# SNES1Chip_SCIC_IGR_D4_Takt.net
KiCad netlist of a schematic drawn in EAGLE
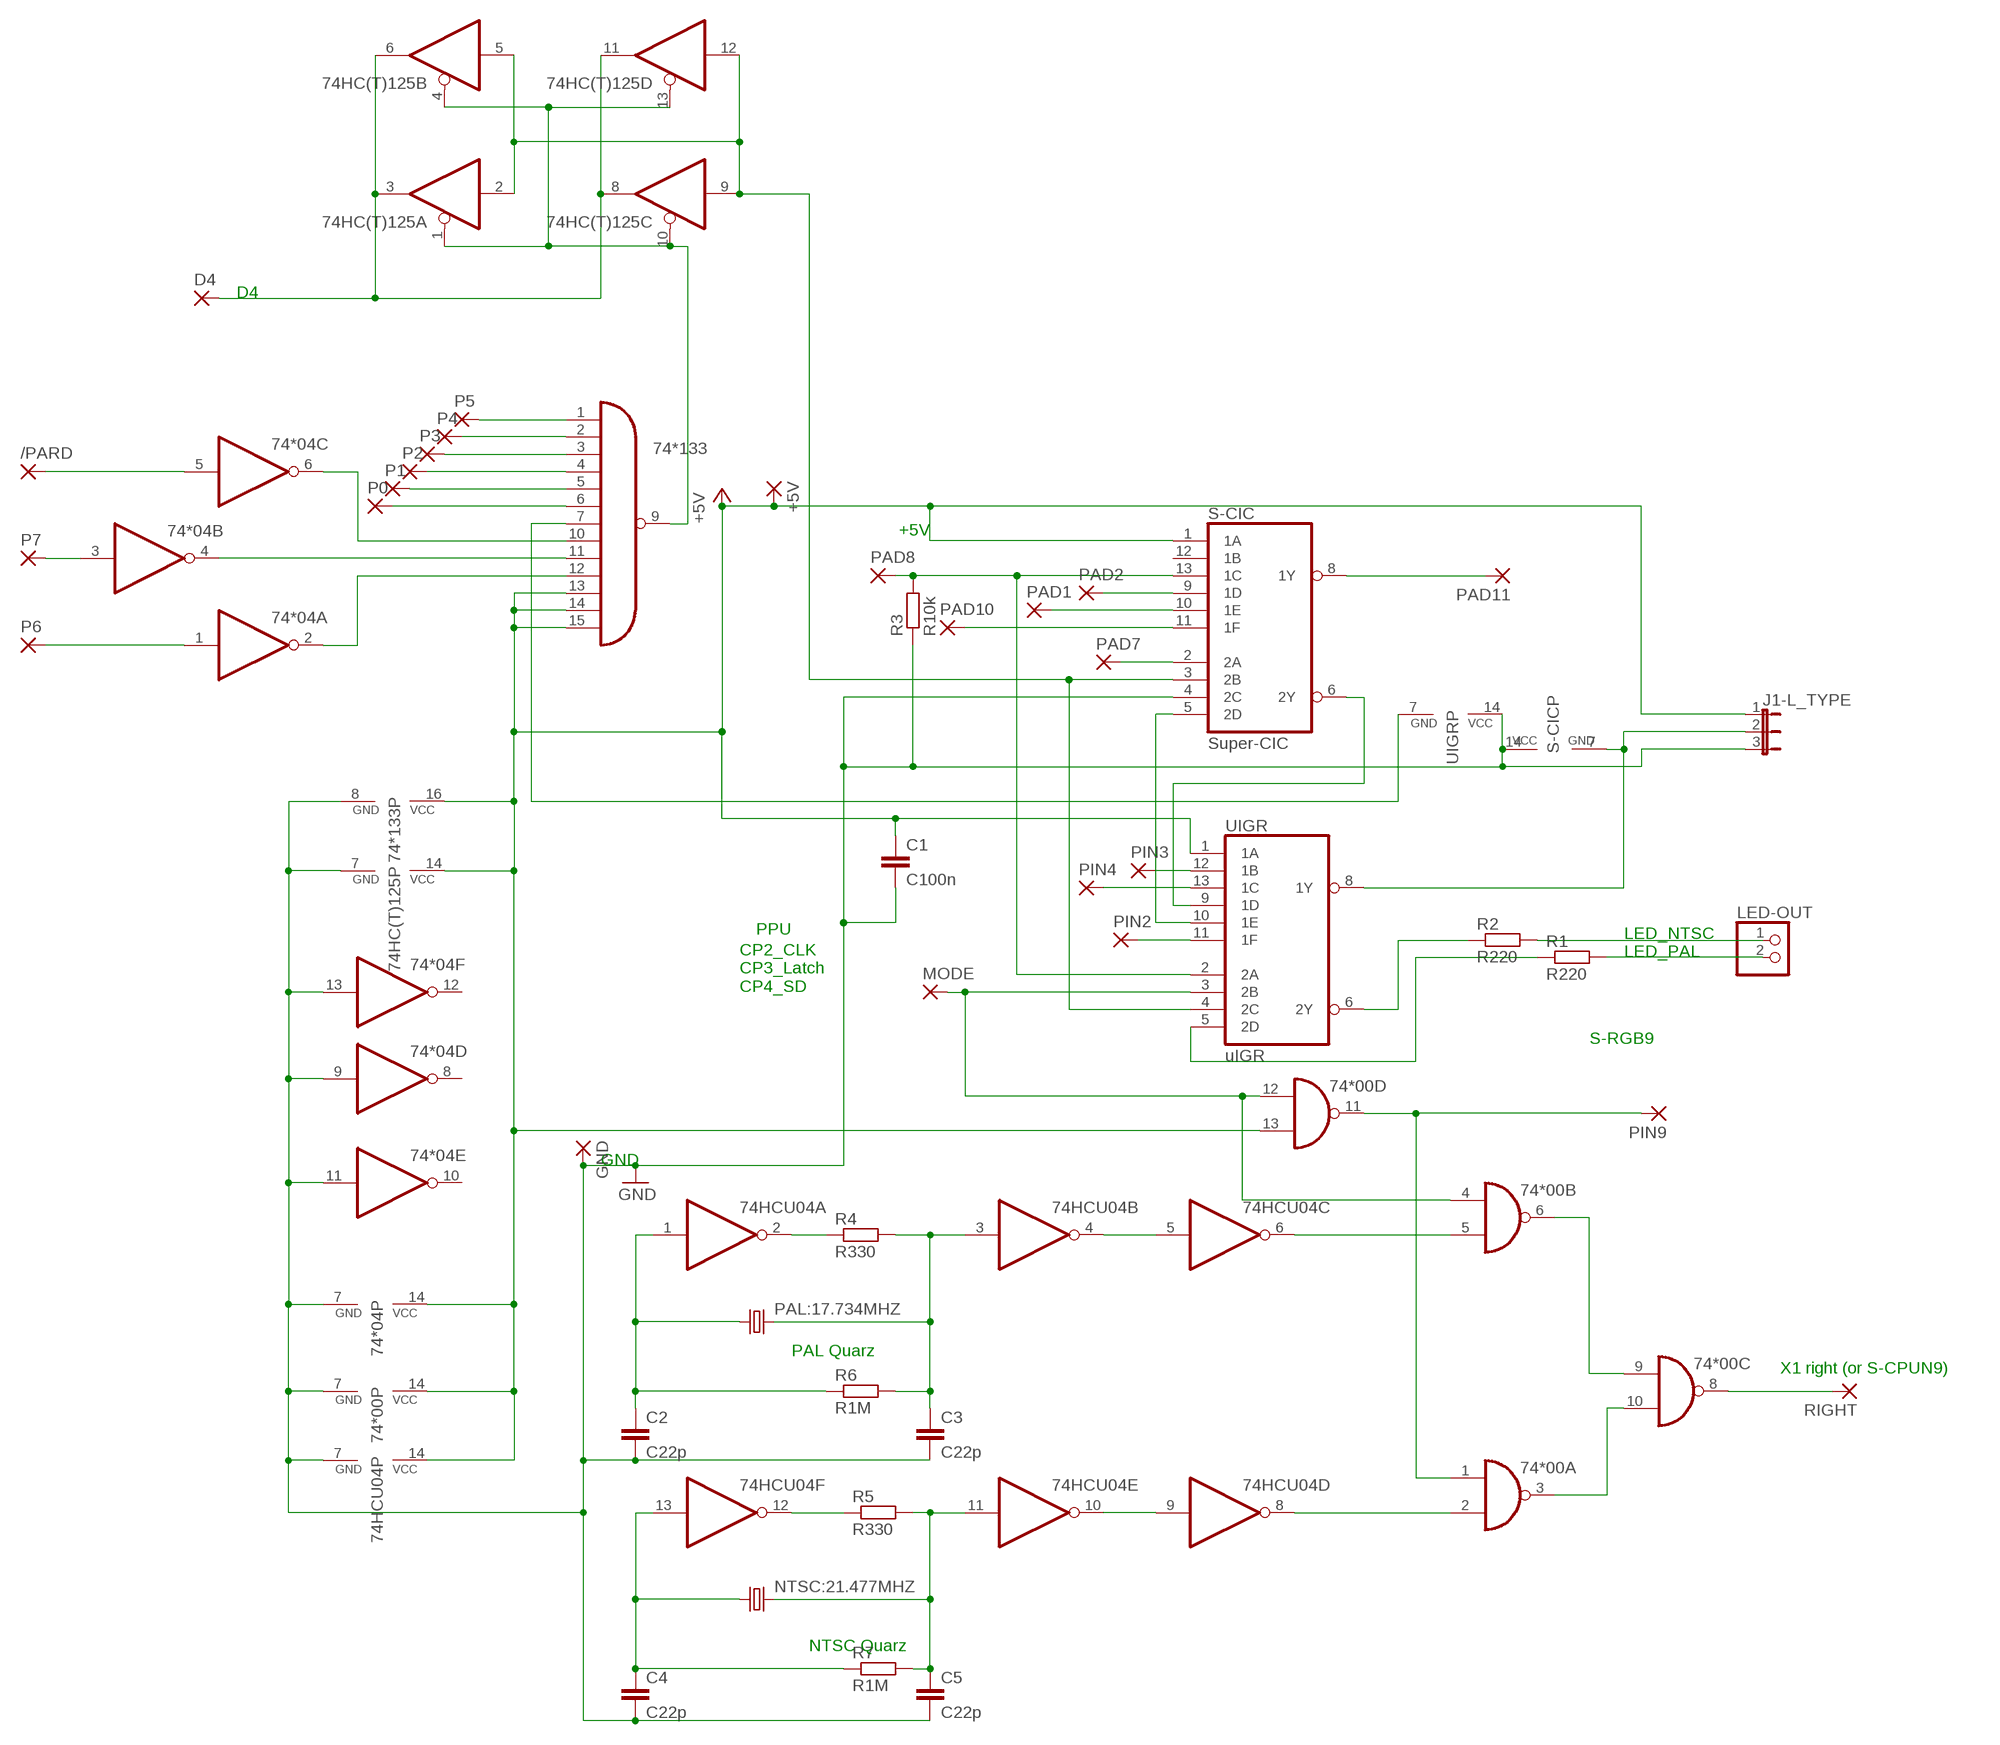
[diagram p0: schematic, sheet 1]

(export (version "E")
  (design (tool "Eeschema 10.0.6"))
  (components
    (comp (ref "+5V")
      (value "2,54/0,8")
      (footprint "eagle-import:2,54_0,8")
      (libsource (lib "eagle-import") (part "2,54/0,8"))
    )
    (comp (ref "/PARD")
      (value "2,54/0,8")
      (footprint "eagle-import:2,54_0,8")
      (libsource (lib "eagle-import") (part "2,54/0,8"))
    )
    (comp (ref "74*00")
      (value "7400D")
      (footprint "eagle-import:SO14")
      (libsource (lib "eagle-import") (part "7400D"))
    )
    (comp (ref "74*04")
      (value "74S04D")
      (footprint "eagle-import:SO14")
      (libsource (lib "eagle-import") (part "7404DS"))
    )
    (comp (ref "74*133")
      (value "74S133D")
      (footprint "eagle-import:SO16")
      (libsource (lib "eagle-import") (part "74133DS"))
    )
    (comp (ref "74HC(T)125")
      (value "74HCT125D")
      (footprint "eagle-import:SO14")
      (libsource (lib "eagle-import") (part "74125DHCT"))
    )
    (comp (ref "74HCU04")
      (value "74HC04D")
      (footprint "eagle-import:SO14")
      (libsource (lib "eagle-import") (part "7404DHC"))
    )
    (comp (ref "C1")
      (value "C100n")
      (footprint "eagle-import:C0805")
      (libsource (lib "eagle-import") (part "C-EUC0805"))
    )
    (comp (ref "C2")
      (value "C22p")
      (footprint "eagle-import:C0805")
      (libsource (lib "eagle-import") (part "C-EUC0805"))
    )
    (comp (ref "C3")
      (value "C22p")
      (footprint "eagle-import:C0805")
      (libsource (lib "eagle-import") (part "C-EUC0805"))
    )
    (comp (ref "C4")
      (value "C22p")
      (footprint "eagle-import:C0805")
      (libsource (lib "eagle-import") (part "C-EUC0805"))
    )
    (comp (ref "C5")
      (value "C22p")
      (footprint "eagle-import:C0805")
      (libsource (lib "eagle-import") (part "C-EUC0805"))
    )
    (comp (ref "D4")
      (value "2,54/0,8")
      (footprint "eagle-import:2,54_0,8")
      (libsource (lib "eagle-import") (part "2,54/0,8"))
    )
    (comp (ref "GND")
      (value "2,54/0,8")
      (footprint "eagle-import:2,54_0,8")
      (libsource (lib "eagle-import") (part "2,54/0,8"))
    )
    (comp (ref "J1-L_TYPE")
      (value "JP2E")
      (footprint "eagle-import:JP2")
      (libsource (lib "eagle-import") (part "JP2E"))
    )
    (comp (ref "LED-OUT")
      (value "PINHD-1X2")
      (footprint "eagle-import:1X02")
      (libsource (lib "eagle-import") (part "PINHD-1X2"))
    )
    (comp (ref "MODE")
      (value "2,54/0,8")
      (footprint "eagle-import:2,54_0,8")
      (libsource (lib "eagle-import") (part "2,54/0,8"))
    )
    (comp (ref "NTSC:21.477MHZ")
      (value "CRYSTALHC49S")
      (footprint "eagle-import:HC49_S")
      (libsource (lib "eagle-import") (part "CRYSTALHC49S"))
    )
    (comp (ref "P0")
      (value "2,54/0,8")
      (footprint "eagle-import:2,54_0,8")
      (libsource (lib "eagle-import") (part "2,54/0,8"))
    )
    (comp (ref "P1")
      (value "2,54/0,8")
      (footprint "eagle-import:2,54_0,8")
      (libsource (lib "eagle-import") (part "2,54/0,8"))
    )
    (comp (ref "P2")
      (value "2,54/0,8")
      (footprint "eagle-import:2,54_0,8")
      (libsource (lib "eagle-import") (part "2,54/0,8"))
    )
    (comp (ref "P3")
      (value "2,54/0,8")
      (footprint "eagle-import:2,54_0,8")
      (libsource (lib "eagle-import") (part "2,54/0,8"))
    )
    (comp (ref "P4")
      (value "2,54/0,8")
      (footprint "eagle-import:2,54_0,8")
      (libsource (lib "eagle-import") (part "2,54/0,8"))
    )
    (comp (ref "P5")
      (value "2,54/0,8")
      (footprint "eagle-import:2,54_0,8")
      (libsource (lib "eagle-import") (part "2,54/0,8"))
    )
    (comp (ref "P6")
      (value "2,54/0,8")
      (footprint "eagle-import:2,54_0,8")
      (libsource (lib "eagle-import") (part "2,54/0,8"))
    )
    (comp (ref "P7")
      (value "2,54/0,8")
      (footprint "eagle-import:2,54_0,8")
      (libsource (lib "eagle-import") (part "2,54/0,8"))
    )
    (comp (ref "PAD1")
      (value "2,54/0,8")
      (footprint "eagle-import:2,54_0,8")
      (libsource (lib "eagle-import") (part "2,54/0,8"))
    )
    (comp (ref "PAD2")
      (value "2,54/0,8")
      (footprint "eagle-import:2,54_0,8")
      (libsource (lib "eagle-import") (part "2,54/0,8"))
    )
    (comp (ref "PAD7")
      (value "2,54/0,8")
      (footprint "eagle-import:2,54_0,8")
      (libsource (lib "eagle-import") (part "2,54/0,8"))
    )
    (comp (ref "PAD8")
      (value "2,54/0,8")
      (footprint "eagle-import:2,54_0,8")
      (libsource (lib "eagle-import") (part "2,54/0,8"))
    )
    (comp (ref "PAD10")
      (value "2,54/0,8")
      (footprint "eagle-import:2,54_0,8")
      (libsource (lib "eagle-import") (part "2,54/0,8"))
    )
    (comp (ref "PAD11")
      (value "2,54/0,8")
      (footprint "eagle-import:2,54_0,8")
      (libsource (lib "eagle-import") (part "2,54/0,8"))
    )
    (comp (ref "PAL:17.734MHZ")
      (value "CRYSTALHC49S")
      (footprint "eagle-import:HC49_S")
      (libsource (lib "eagle-import") (part "CRYSTALHC49S"))
    )
    (comp (ref "PIN2")
      (value "2,54/0,8")
      (footprint "eagle-import:2,54_0,8")
      (libsource (lib "eagle-import") (part "2,54/0,8"))
    )
    (comp (ref "PIN3")
      (value "2,54/0,8")
      (footprint "eagle-import:2,54_0,8")
      (libsource (lib "eagle-import") (part "2,54/0,8"))
    )
    (comp (ref "PIN4")
      (value "2,54/0,8")
      (footprint "eagle-import:2,54_0,8")
      (libsource (lib "eagle-import") (part "2,54/0,8"))
    )
    (comp (ref "PIN9")
      (value "2,54/0,8")
      (footprint "eagle-import:2,54_0,8")
      (libsource (lib "eagle-import") (part "2,54/0,8"))
    )
    (comp (ref "R1")
      (value "R220")
      (footprint "eagle-import:R0805")
      (libsource (lib "eagle-import") (part "R-EU_R0805"))
    )
    (comp (ref "R2")
      (value "R220")
      (footprint "eagle-import:R0805")
      (libsource (lib "eagle-import") (part "R-EU_R0805"))
    )
    (comp (ref "R3")
      (value "R10k")
      (footprint "eagle-import:R0805")
      (libsource (lib "eagle-import") (part "R-EU_R0805"))
    )
    (comp (ref "R4")
      (value "R330")
      (footprint "eagle-import:R0805")
      (libsource (lib "eagle-import") (part "R-EU_R0805"))
    )
    (comp (ref "R5")
      (value "R330")
      (footprint "eagle-import:R0805")
      (libsource (lib "eagle-import") (part "R-EU_R0805"))
    )
    (comp (ref "R6")
      (value "R1M")
      (footprint "eagle-import:R0805")
      (libsource (lib "eagle-import") (part "R-EU_R0805"))
    )
    (comp (ref "R7")
      (value "R1M")
      (footprint "eagle-import:R0805")
      (libsource (lib "eagle-import") (part "R-EU_R0805"))
    )
    (comp (ref "RIGHT")
      (value "2,54/0,8")
      (footprint "eagle-import:2,54_0,8")
      (libsource (lib "eagle-import") (part "2,54/0,8"))
    )
    (comp (ref "S-CIC")
      (value "Super-CIC")
      (footprint "eagle-import:SO14")
      (libsource (lib "eagle-import") (part "7451DHC"))
    )
    (comp (ref "UIGR")
      (value "uIGR")
      (footprint "eagle-import:SO14")
      (libsource (lib "eagle-import") (part "7451DHC"))
    )
  )
  (nets
    (net (code "1") (name "+5V") (class "Default")
      (node (ref "+5V") (pin "1") (pinfunction "P_1") (pintype "passive"))
      (node (ref "74*00") (pin "13") (pinfunction "I1_13") (pintype "input"))
      (node (ref "74*00") (pin "14") (pinfunction "VCC_14") (pintype "power_in"))
      (node (ref "74*04") (pin "14") (pinfunction "VCC_14") (pintype "power_in"))
      (node (ref "74*133") (pin "13") (pinfunction "I10_13") (pintype "input"))
      (node (ref "74*133") (pin "14") (pinfunction "I11_14") (pintype "input"))
      (node (ref "74*133") (pin "15") (pinfunction "I12_15") (pintype "input"))
      (node (ref "74*133") (pin "16") (pinfunction "VCC_16") (pintype "power_in"))
      (node (ref "74HC(T)125") (pin "14") (pinfunction "VCC_14") (pintype "power_in"))
      (node (ref "74HCU04") (pin "14") (pinfunction "VCC_14") (pintype "power_in"))
      (node (ref "C1") (pin "1") (pinfunction "1_1") (pintype "passive"))
      (node (ref "J1-L_TYPE") (pin "1") (pinfunction "1_1") (pintype "passive"))
      (node (ref "S-CIC") (pin "1") (pinfunction "1A_1") (pintype "input"))
      (node (ref "UIGR") (pin "1") (pinfunction "1A_1") (pintype "input"))
    )
    (net (code "2") (name "GND") (class "Default")
      (node (ref "74*00") (pin "7") (pinfunction "GND_7") (pintype "power_in"))
      (node (ref "74*04") (pin "11") (pinfunction "I_11") (pintype "input"))
      (node (ref "74*04") (pin "13") (pinfunction "I_13") (pintype "input"))
      (node (ref "74*04") (pin "7") (pinfunction "GND_7") (pintype "power_in"))
      (node (ref "74*04") (pin "9") (pinfunction "I_9") (pintype "input"))
      (node (ref "74*133") (pin "8") (pinfunction "GND_8") (pintype "power_in"))
      (node (ref "74HC(T)125") (pin "7") (pinfunction "GND_7") (pintype "power_in"))
      (node (ref "74HCU04") (pin "7") (pinfunction "GND_7") (pintype "power_in"))
      (node (ref "C1") (pin "2") (pinfunction "2_2") (pintype "passive"))
      (node (ref "C2") (pin "2") (pinfunction "2_2") (pintype "passive"))
      (node (ref "C3") (pin "2") (pinfunction "2_2") (pintype "passive"))
      (node (ref "C4") (pin "2") (pinfunction "2_2") (pintype "passive"))
      (node (ref "C5") (pin "2") (pinfunction "2_2") (pintype "passive"))
      (node (ref "GND") (pin "1") (pinfunction "P_1") (pintype "passive"))
      (node (ref "J1-L_TYPE") (pin "3") (pinfunction "3_3") (pintype "passive"))
      (node (ref "R3") (pin "1") (pinfunction "1_1") (pintype "passive"))
      (node (ref "S-CIC") (pin "14") (pinfunction "VCC_14") (pintype "power_in"))
      (node (ref "S-CIC") (pin "4") (pinfunction "2C_4") (pintype "input"))
      (node (ref "UIGR") (pin "14") (pinfunction "VCC_14") (pintype "power_in"))
    )
    (net (code "3") (name "Net-(/PARD-P)") (class "Default")
      (node (ref "/PARD") (pin "1") (pinfunction "P_1") (pintype "passive"))
      (node (ref "74*04") (pin "5") (pinfunction "I_5") (pintype "input"))
    )
    (net (code "4") (name "Net-(74*00A-I0)") (class "Default")
      (node (ref "74*00") (pin "1") (pinfunction "I0_1") (pintype "input"))
      (node (ref "74*00") (pin "11") (pinfunction "O_11") (pintype "output"))
      (node (ref "PIN9") (pin "1") (pinfunction "P_1") (pintype "passive"))
    )
    (net (code "5") (name "Net-(74*00A-I1)") (class "Default")
      (node (ref "74*00") (pin "2") (pinfunction "I1_2") (pintype "input"))
      (node (ref "74HCU04") (pin "8") (pinfunction "O_8") (pintype "output"))
    )
    (net (code "6") (name "Net-(74*00A-O)") (class "Default")
      (node (ref "74*00") (pin "10") (pinfunction "I1_10") (pintype "input"))
      (node (ref "74*00") (pin "3") (pinfunction "O_3") (pintype "output"))
    )
    (net (code "7") (name "Net-(74*00B-I0)") (class "Default")
      (node (ref "74*00") (pin "12") (pinfunction "I0_12") (pintype "input"))
      (node (ref "74*00") (pin "4") (pinfunction "I0_4") (pintype "input"))
      (node (ref "MODE") (pin "1") (pinfunction "P_1") (pintype "passive"))
      (node (ref "UIGR") (pin "3") (pinfunction "2B_3") (pintype "input"))
    )
    (net (code "8") (name "Net-(74*00B-I1)") (class "Default")
      (node (ref "74*00") (pin "5") (pinfunction "I1_5") (pintype "input"))
      (node (ref "74HCU04") (pin "6") (pinfunction "O_6") (pintype "output"))
    )
    (net (code "9") (name "Net-(74*00B-O)") (class "Default")
      (node (ref "74*00") (pin "6") (pinfunction "O_6") (pintype "output"))
      (node (ref "74*00") (pin "9") (pinfunction "I0_9") (pintype "input"))
    )
    (net (code "10") (name "Net-(74*00C-O)") (class "Default")
      (node (ref "74*00") (pin "8") (pinfunction "O_8") (pintype "output"))
      (node (ref "RIGHT") (pin "1") (pinfunction "P_1") (pintype "passive"))
    )
    (net (code "11") (name "Net-(74*04A-I)") (class "Default")
      (node (ref "74*04") (pin "1") (pinfunction "I_1") (pintype "input"))
      (node (ref "P6") (pin "1") (pinfunction "P_1") (pintype "passive"))
    )
    (net (code "12") (name "Net-(74*04A-O)") (class "Default")
      (node (ref "74*04") (pin "2") (pinfunction "O_2") (pintype "output"))
      (node (ref "74*133") (pin "12") (pinfunction "I9_12") (pintype "input"))
    )
    (net (code "13") (name "Net-(74*04B-I)") (class "Default")
      (node (ref "74*04") (pin "3") (pinfunction "I_3") (pintype "input"))
      (node (ref "P7") (pin "1") (pinfunction "P_1") (pintype "passive"))
    )
    (net (code "14") (name "Net-(74*04B-O)") (class "Default")
      (node (ref "74*04") (pin "4") (pinfunction "O_4") (pintype "output"))
      (node (ref "74*133") (pin "11") (pinfunction "I8_11") (pintype "input"))
    )
    (net (code "15") (name "Net-(74*04C-O)") (class "Default")
      (node (ref "74*04") (pin "6") (pinfunction "O_6") (pintype "output"))
      (node (ref "74*133") (pin "10") (pinfunction "I7_10") (pintype "input"))
    )
    (net (code "16") (name "Net-(74*133A-I0)") (class "Default")
      (node (ref "74*133") (pin "1") (pinfunction "I0_1") (pintype "input"))
      (node (ref "P5") (pin "1") (pinfunction "P_1") (pintype "passive"))
    )
    (net (code "17") (name "Net-(74*133A-I1)") (class "Default")
      (node (ref "74*133") (pin "2") (pinfunction "I1_2") (pintype "input"))
      (node (ref "P4") (pin "1") (pinfunction "P_1") (pintype "passive"))
    )
    (net (code "18") (name "Net-(74*133A-I2)") (class "Default")
      (node (ref "74*133") (pin "3") (pinfunction "I2_3") (pintype "input"))
      (node (ref "P3") (pin "1") (pinfunction "P_1") (pintype "passive"))
    )
    (net (code "19") (name "Net-(74*133A-I3)") (class "Default")
      (node (ref "74*133") (pin "4") (pinfunction "I3_4") (pintype "input"))
      (node (ref "P2") (pin "1") (pinfunction "P_1") (pintype "passive"))
    )
    (net (code "20") (name "Net-(74*133A-I4)") (class "Default")
      (node (ref "74*133") (pin "5") (pinfunction "I4_5") (pintype "input"))
      (node (ref "P1") (pin "1") (pinfunction "P_1") (pintype "passive"))
    )
    (net (code "21") (name "Net-(74*133A-I5)") (class "Default")
      (node (ref "74*133") (pin "6") (pinfunction "I5_6") (pintype "input"))
      (node (ref "P0") (pin "1") (pinfunction "P_1") (pintype "passive"))
    )
    (net (code "22") (name "Net-(74*133A-I6)") (class "Default")
      (node (ref "74*133") (pin "7") (pinfunction "I6_7") (pintype "input"))
      (node (ref "UIGR") (pin "7") (pinfunction "GND_7") (pintype "power_in"))
    )
    (net (code "23") (name "Net-(74*133A-O)") (class "Default")
      (node (ref "74*133") (pin "9") (pinfunction "O_9") (pintype "output"))
      (node (ref "74HC(T)125") (pin "1") (pinfunction "OE_1") (pintype "input"))
      (node (ref "74HC(T)125") (pin "10") (pinfunction "OE_10") (pintype "input"))
      (node (ref "74HC(T)125") (pin "13") (pinfunction "OE_13") (pintype "input"))
      (node (ref "74HC(T)125") (pin "4") (pinfunction "OE_4") (pintype "input"))
    )
    (net (code "24") (name "Net-(74HC(T)125A-I)") (class "Default")
      (node (ref "74HC(T)125") (pin "12") (pinfunction "I_12") (pintype "input"))
      (node (ref "74HC(T)125") (pin "2") (pinfunction "I_2") (pintype "input"))
      (node (ref "74HC(T)125") (pin "5") (pinfunction "I_5") (pintype "input"))
      (node (ref "74HC(T)125") (pin "9") (pinfunction "I_9") (pintype "input"))
      (node (ref "S-CIC") (pin "3") (pinfunction "2B_3") (pintype "input"))
      (node (ref "UIGR") (pin "4") (pinfunction "2C_4") (pintype "input"))
    )
    (net (code "25") (name "Net-(74HC(T)125A-O)") (class "Default")
      (node (ref "74HC(T)125") (pin "11") (pinfunction "O_11") (pintype "tri_state"))
      (node (ref "74HC(T)125") (pin "3") (pinfunction "O_3") (pintype "tri_state"))
      (node (ref "74HC(T)125") (pin "6") (pinfunction "O_6") (pintype "tri_state"))
      (node (ref "74HC(T)125") (pin "8") (pinfunction "O_8") (pintype "tri_state"))
      (node (ref "D4") (pin "1") (pinfunction "P_1") (pintype "passive"))
    )
    (net (code "26") (name "Net-(74HCU04A-I)") (class "Default")
      (node (ref "74HCU04") (pin "1") (pinfunction "I_1") (pintype "input"))
      (node (ref "C2") (pin "1") (pinfunction "1_1") (pintype "passive"))
      (node (ref "PAL:17.734MHZ") (pin "1") (pinfunction "1_1") (pintype "passive"))
      (node (ref "R6") (pin "1") (pinfunction "1_1") (pintype "passive"))
    )
    (net (code "27") (name "Net-(74HCU04A-O)") (class "Default")
      (node (ref "74HCU04") (pin "2") (pinfunction "O_2") (pintype "output"))
      (node (ref "R4") (pin "1") (pinfunction "1_1") (pintype "passive"))
    )
    (net (code "28") (name "Net-(74HCU04B-I)") (class "Default")
      (node (ref "74HCU04") (pin "3") (pinfunction "I_3") (pintype "input"))
      (node (ref "C3") (pin "1") (pinfunction "1_1") (pintype "passive"))
      (node (ref "PAL:17.734MHZ") (pin "2") (pinfunction "2_2") (pintype "passive"))
      (node (ref "R4") (pin "2") (pinfunction "2_2") (pintype "passive"))
      (node (ref "R6") (pin "2") (pinfunction "2_2") (pintype "passive"))
    )
    (net (code "29") (name "Net-(74HCU04B-O)") (class "Default")
      (node (ref "74HCU04") (pin "4") (pinfunction "O_4") (pintype "output"))
      (node (ref "74HCU04") (pin "5") (pinfunction "I_5") (pintype "input"))
    )
    (net (code "30") (name "Net-(74HCU04D-I)") (class "Default")
      (node (ref "74HCU04") (pin "10") (pinfunction "O_10") (pintype "output"))
      (node (ref "74HCU04") (pin "9") (pinfunction "I_9") (pintype "input"))
    )
    (net (code "31") (name "Net-(74HCU04E-I)") (class "Default")
      (node (ref "74HCU04") (pin "11") (pinfunction "I_11") (pintype "input"))
      (node (ref "C5") (pin "1") (pinfunction "1_1") (pintype "passive"))
      (node (ref "NTSC:21.477MHZ") (pin "2") (pinfunction "2_2") (pintype "passive"))
      (node (ref "R5") (pin "2") (pinfunction "2_2") (pintype "passive"))
      (node (ref "R7") (pin "2") (pinfunction "2_2") (pintype "passive"))
    )
    (net (code "32") (name "Net-(74HCU04F-I)") (class "Default")
      (node (ref "74HCU04") (pin "13") (pinfunction "I_13") (pintype "input"))
      (node (ref "C4") (pin "1") (pinfunction "1_1") (pintype "passive"))
      (node (ref "NTSC:21.477MHZ") (pin "1") (pinfunction "1_1") (pintype "passive"))
      (node (ref "R7") (pin "1") (pinfunction "1_1") (pintype "passive"))
    )
    (net (code "33") (name "Net-(74HCU04F-O)") (class "Default")
      (node (ref "74HCU04") (pin "12") (pinfunction "O_12") (pintype "output"))
      (node (ref "R5") (pin "1") (pinfunction "1_1") (pintype "passive"))
    )
    (net (code "34") (name "Net-(LED-OUT-Pad1)") (class "Default")
      (node (ref "LED-OUT") (pin "1") (pinfunction "1_1") (pintype "passive"))
      (node (ref "R2") (pin "2") (pinfunction "2_2") (pintype "passive"))
    )
    (net (code "35") (name "Net-(LED-OUT-Pad2)") (class "Default")
      (node (ref "LED-OUT") (pin "2") (pinfunction "2_2") (pintype "passive"))
      (node (ref "R1") (pin "2") (pinfunction "2_2") (pintype "passive"))
    )
    (net (code "36") (name "Net-(PAD1-P)") (class "Default")
      (node (ref "PAD1") (pin "1") (pinfunction "P_1") (pintype "passive"))
      (node (ref "S-CIC") (pin "10") (pinfunction "1E_10") (pintype "input"))
    )
    (net (code "37") (name "Net-(PAD2-P)") (class "Default")
      (node (ref "PAD2") (pin "1") (pinfunction "P_1") (pintype "passive"))
      (node (ref "S-CIC") (pin "9") (pinfunction "1D_9") (pintype "input"))
    )
    (net (code "38") (name "Net-(PAD7-P)") (class "Default")
      (node (ref "PAD7") (pin "1") (pinfunction "P_1") (pintype "passive"))
      (node (ref "S-CIC") (pin "2") (pinfunction "2A_2") (pintype "input"))
    )
    (net (code "39") (name "Net-(PAD8-P)") (class "Default")
      (node (ref "PAD8") (pin "1") (pinfunction "P_1") (pintype "passive"))
      (node (ref "R3") (pin "2") (pinfunction "2_2") (pintype "passive"))
      (node (ref "S-CIC") (pin "13") (pinfunction "1C_13") (pintype "input"))
      (node (ref "UIGR") (pin "2") (pinfunction "2A_2") (pintype "input"))
    )
    (net (code "40") (name "Net-(PAD10-P)") (class "Default")
      (node (ref "PAD10") (pin "1") (pinfunction "P_1") (pintype "passive"))
      (node (ref "S-CIC") (pin "11") (pinfunction "1F_11") (pintype "input"))
    )
    (net (code "41") (name "Net-(PAD11-P)") (class "Default")
      (node (ref "PAD11") (pin "1") (pinfunction "P_1") (pintype "passive"))
      (node (ref "S-CIC") (pin "8") (pinfunction "1Y_8") (pintype "output"))
    )
    (net (code "42") (name "Net-(PIN2-P)") (class "Default")
      (node (ref "PIN2") (pin "1") (pinfunction "P_1") (pintype "passive"))
      (node (ref "UIGR") (pin "11") (pinfunction "1F_11") (pintype "input"))
    )
    (net (code "43") (name "Net-(PIN3-P)") (class "Default")
      (node (ref "PIN3") (pin "1") (pinfunction "P_1") (pintype "passive"))
      (node (ref "UIGR") (pin "12") (pinfunction "1B_12") (pintype "input"))
    )
    (net (code "44") (name "Net-(PIN4-P)") (class "Default")
      (node (ref "PIN4") (pin "1") (pinfunction "P_1") (pintype "passive"))
      (node (ref "UIGR") (pin "13") (pinfunction "1C_13") (pintype "input"))
    )
    (net (code "45") (name "Net-(S-CICA-2D)") (class "Default")
      (node (ref "S-CIC") (pin "5") (pinfunction "2D_5") (pintype "input"))
      (node (ref "UIGR") (pin "10") (pinfunction "1E_10") (pintype "input"))
    )
    (net (code "46") (name "Net-(S-CICA-2Y)") (class "Default")
      (node (ref "S-CIC") (pin "6") (pinfunction "2Y_6") (pintype "output"))
      (node (ref "UIGR") (pin "9") (pinfunction "1D_9") (pintype "input"))
    )
    (net (code "47") (name "Net-(S-CICB-GND)") (class "Default")
      (node (ref "J1-L_TYPE") (pin "2") (pinfunction "2_2") (pintype "passive"))
      (node (ref "S-CIC") (pin "7") (pinfunction "GND_7") (pintype "power_in"))
      (node (ref "UIGR") (pin "8") (pinfunction "1Y_8") (pintype "output"))
    )
    (net (code "48") (name "Net-(UIGRA-2D)") (class "Default")
      (node (ref "R1") (pin "1") (pinfunction "1_1") (pintype "passive"))
      (node (ref "UIGR") (pin "5") (pinfunction "2D_5") (pintype "input"))
    )
    (net (code "49") (name "Net-(UIGRA-2Y)") (class "Default")
      (node (ref "R2") (pin "1") (pinfunction "1_1") (pintype "passive"))
      (node (ref "UIGR") (pin "6") (pinfunction "2Y_6") (pintype "output"))
    )
    (net (code "50") (name "unconnected-(74*04D-O-Pad8)") (class "Default")
      (node (ref "74*04") (pin "8") (pinfunction "O_8") (pintype "output"))
    )
    (net (code "51") (name "unconnected-(74*04E-O-Pad10)") (class "Default")
      (node (ref "74*04") (pin "10") (pinfunction "O_10") (pintype "output"))
    )
    (net (code "52") (name "unconnected-(74*04F-O-Pad12)") (class "Default")
      (node (ref "74*04") (pin "12") (pinfunction "O_12") (pintype "output"))
    )
    (net (code "53") (name "unconnected-(S-CICA-1B-Pad12)") (class "Default")
      (node (ref "S-CIC") (pin "12") (pinfunction "1B_12") (pintype "input"))
    )
  )
)
